# remote.net
KiCad netlist of a schematic drawn in EAGLE
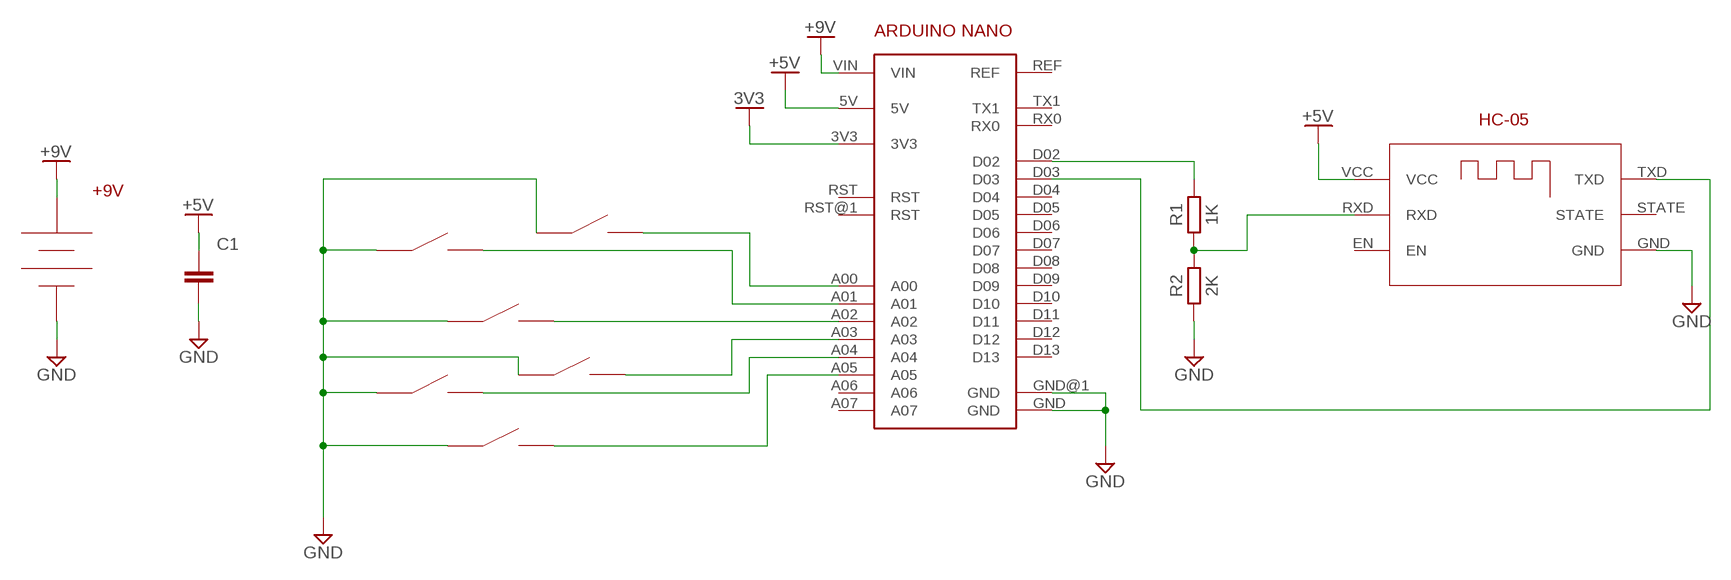
[diagram p0: schematic, sheet 1]

(export (version "E")
  (design (tool "Eeschema 10.0.6"))
  (components
    (comp (ref "C1")
      (value "C_RADIAL-12.5MM-DIA")
      (footprint "eagle-import:CAPRD550W60D1025H1250B")
      (libsource (lib "eagle-import") (part "CRADIAL-12.5MM-DIA_"))
    )
    (comp (ref "DOWN")
      (value "TACT_SWITCH_6MM")
      (footprint "eagle-import:TACT_SWITCH_6MM")
      (libsource (lib "eagle-import") (part "TACT_SWITCH_6MM"))
    )
    (comp (ref "LEFT")
      (value "TACT_SWITCH_6MM")
      (footprint "eagle-import:TACT_SWITCH_6MM")
      (libsource (lib "eagle-import") (part "TACT_SWITCH_6MM"))
    )
    (comp (ref "LEFT_BUMPER")
      (value "TACT_SWITCH_6MM")
      (footprint "eagle-import:TACT_SWITCH_6MM")
      (libsource (lib "eagle-import") (part "TACT_SWITCH_6MM"))
    )
    (comp (ref "R1")
      (value "1K")
      (footprint "eagle-import:RESAD1176W63L850D250B")
      (libsource (lib "eagle-import") (part "RAXIAL-11.7MM-PITCH_"))
    )
    (comp (ref "R2")
      (value "2K")
      (footprint "eagle-import:RESAD1176W63L850D250B")
      (libsource (lib "eagle-import") (part "RAXIAL-11.7MM-PITCH_"))
    )
    (comp (ref "RIGHT")
      (value "TACT_SWITCH_6MM")
      (footprint "eagle-import:TACT_SWITCH_6MM")
      (libsource (lib "eagle-import") (part "TACT_SWITCH_6MM"))
    )
    (comp (ref "RIGHT_BUMPER")
      (value "TACT_SWITCH_6MM")
      (footprint "eagle-import:TACT_SWITCH_6MM")
      (libsource (lib "eagle-import") (part "TACT_SWITCH_6MM"))
    )
    (comp (ref "U$1")
      (value "9V_BATTERY")
      (footprint "eagle-import:9V_BATTERY")
      (libsource (lib "eagle-import") (part "9V_BATTERY"))
    )
    (comp (ref "U$2")
      (value "HC-05")
      (footprint "eagle-import:HC-05")
      (libsource (lib "eagle-import") (part "HC-05"))
    )
    (comp (ref "U$9")
      (value "ARDUINO-NANO-V3")
      (footprint "eagle-import:ARDUINO-NANO-V3")
      (libsource (lib "eagle-import") (part "ARDUINO-NANO-V3"))
    )
    (comp (ref "UP")
      (value "TACT_SWITCH_6MM")
      (footprint "eagle-import:TACT_SWITCH_6MM")
      (libsource (lib "eagle-import") (part "TACT_SWITCH_6MM"))
    )
  )
  (nets
    (net (code "1") (name "+5V") (class "Default")
      (node (ref "C1") (pin "1") (pinfunction "1_1") (pintype "passive"))
      (node (ref "U$2") (pin "VCC") (pinfunction "VCC_VCC") (pintype "bidirectional"))
      (node (ref "U$9") (pin "5V") (pinfunction "5V_5V") (pintype "bidirectional"))
    )
    (net (code "2") (name "+9V") (class "Default")
      (node (ref "U$1") (pin "POS") (pinfunction "9V_POS") (pintype "bidirectional"))
      (node (ref "U$9") (pin "VIN") (pinfunction "VIN_VIN") (pintype "bidirectional"))
    )
    (net (code "3") (name "3V3") (class "Default")
      (node (ref "U$9") (pin "3V3") (pinfunction "3V3_3V3") (pintype "bidirectional"))
    )
    (net (code "4") (name "GND") (class "Default")
      (node (ref "C1") (pin "2") (pinfunction "2_2") (pintype "passive"))
      (node (ref "DOWN") (pin "A1") (pinfunction "A_A1") (pintype "bidirectional"))
      (node (ref "DOWN") (pin "A2") (pinfunction "A_A2") (pintype "bidirectional"))
      (node (ref "LEFT") (pin "A1") (pinfunction "A_A1") (pintype "bidirectional"))
      (node (ref "LEFT") (pin "A2") (pinfunction "A_A2") (pintype "bidirectional"))
      (node (ref "LEFT_BUMPER") (pin "A1") (pinfunction "A_A1") (pintype "bidirectional"))
      (node (ref "LEFT_BUMPER") (pin "A2") (pinfunction "A_A2") (pintype "bidirectional"))
      (node (ref "R2") (pin "1") (pinfunction "1_1") (pintype "passive"))
      (node (ref "RIGHT") (pin "A1") (pinfunction "A_A1") (pintype "bidirectional"))
      (node (ref "RIGHT") (pin "A2") (pinfunction "A_A2") (pintype "bidirectional"))
      (node (ref "RIGHT_BUMPER") (pin "A1") (pinfunction "A_A1") (pintype "bidirectional"))
      (node (ref "RIGHT_BUMPER") (pin "A2") (pinfunction "A_A2") (pintype "bidirectional"))
      (node (ref "U$1") (pin "NEG") (pinfunction "NEG_NEG") (pintype "bidirectional"))
      (node (ref "U$2") (pin "GND") (pinfunction "GND_GND") (pintype "bidirectional"))
      (node (ref "U$9") (pin "GND") (pinfunction "GND_GND") (pintype "bidirectional"))
      (node (ref "U$9") (pin "GND@1") (pinfunction "GND_GND@1") (pintype "bidirectional"))
      (node (ref "UP") (pin "A1") (pinfunction "A_A1") (pintype "bidirectional"))
      (node (ref "UP") (pin "A2") (pinfunction "A_A2") (pintype "bidirectional"))
    )
    (net (code "5") (name "Net-(DOWN-B-PadB1)") (class "Default")
      (node (ref "DOWN") (pin "B1") (pinfunction "B_B1") (pintype "bidirectional"))
      (node (ref "DOWN") (pin "B2") (pinfunction "B_B2") (pintype "bidirectional"))
      (node (ref "U$9") (pin "A05") (pinfunction "A05_A05") (pintype "bidirectional"))
    )
    (net (code "6") (name "Net-(LEFT-B-PadB1)") (class "Default")
      (node (ref "LEFT") (pin "B1") (pinfunction "B_B1") (pintype "bidirectional"))
      (node (ref "LEFT") (pin "B2") (pinfunction "B_B2") (pintype "bidirectional"))
      (node (ref "U$9") (pin "A04") (pinfunction "A04_A04") (pintype "bidirectional"))
    )
    (net (code "7") (name "Net-(LEFT_BUMPER-B-PadB1)") (class "Default")
      (node (ref "LEFT_BUMPER") (pin "B1") (pinfunction "B_B1") (pintype "bidirectional"))
      (node (ref "LEFT_BUMPER") (pin "B2") (pinfunction "B_B2") (pintype "bidirectional"))
      (node (ref "U$9") (pin "A01") (pinfunction "A01_A01") (pintype "bidirectional"))
    )
    (net (code "8") (name "Net-(R1-Pad1)") (class "Default")
      (node (ref "R1") (pin "1") (pinfunction "1_1") (pintype "passive"))
      (node (ref "R2") (pin "2") (pinfunction "2_2") (pintype "passive"))
      (node (ref "U$2") (pin "RXD") (pinfunction "RXD_RXD") (pintype "bidirectional"))
    )
    (net (code "9") (name "Net-(R1-Pad2)") (class "Default")
      (node (ref "R1") (pin "2") (pinfunction "2_2") (pintype "passive"))
      (node (ref "U$9") (pin "D02") (pinfunction "D02_D02") (pintype "bidirectional"))
    )
    (net (code "10") (name "Net-(RIGHT-B-PadB1)") (class "Default")
      (node (ref "RIGHT") (pin "B1") (pinfunction "B_B1") (pintype "bidirectional"))
      (node (ref "RIGHT") (pin "B2") (pinfunction "B_B2") (pintype "bidirectional"))
      (node (ref "U$9") (pin "A03") (pinfunction "A03_A03") (pintype "bidirectional"))
    )
    (net (code "11") (name "Net-(RIGHT_BUMPER-B-PadB1)") (class "Default")
      (node (ref "RIGHT_BUMPER") (pin "B1") (pinfunction "B_B1") (pintype "bidirectional"))
      (node (ref "RIGHT_BUMPER") (pin "B2") (pinfunction "B_B2") (pintype "bidirectional"))
      (node (ref "U$9") (pin "A00") (pinfunction "A00_A00") (pintype "bidirectional"))
    )
    (net (code "12") (name "Net-(U$2-PadTXD)") (class "Default")
      (node (ref "U$2") (pin "TXD") (pinfunction "TXD_TXD") (pintype "bidirectional"))
      (node (ref "U$9") (pin "D03") (pinfunction "D03_D03") (pintype "bidirectional"))
    )
    (net (code "13") (name "Net-(U$9-PadA02)") (class "Default")
      (node (ref "U$9") (pin "A02") (pinfunction "A02_A02") (pintype "bidirectional"))
      (node (ref "UP") (pin "B1") (pinfunction "B_B1") (pintype "bidirectional"))
      (node (ref "UP") (pin "B2") (pinfunction "B_B2") (pintype "bidirectional"))
    )
    (net (code "14") (name "unconnected-(U$2-PadEN)") (class "Default")
      (node (ref "U$2") (pin "EN") (pinfunction "EN_EN") (pintype "bidirectional"))
    )
    (net (code "15") (name "unconnected-(U$2-PadSTATE)") (class "Default")
      (node (ref "U$2") (pin "STATE") (pinfunction "STATE_STATE") (pintype "bidirectional"))
    )
    (net (code "16") (name "unconnected-(U$9-PadA06)") (class "Default")
      (node (ref "U$9") (pin "A06") (pinfunction "A06_A06") (pintype "bidirectional"))
    )
    (net (code "17") (name "unconnected-(U$9-PadA07)") (class "Default")
      (node (ref "U$9") (pin "A07") (pinfunction "A07_A07") (pintype "bidirectional"))
    )
    (net (code "18") (name "unconnected-(U$9-PadD04)") (class "Default")
      (node (ref "U$9") (pin "D04") (pinfunction "D04_D04") (pintype "bidirectional"))
    )
    (net (code "19") (name "unconnected-(U$9-PadD05)") (class "Default")
      (node (ref "U$9") (pin "D05") (pinfunction "D05_D05") (pintype "bidirectional"))
    )
    (net (code "20") (name "unconnected-(U$9-PadD06)") (class "Default")
      (node (ref "U$9") (pin "D06") (pinfunction "D06_D06") (pintype "bidirectional"))
    )
    (net (code "21") (name "unconnected-(U$9-PadD07)") (class "Default")
      (node (ref "U$9") (pin "D07") (pinfunction "D07_D07") (pintype "bidirectional"))
    )
    (net (code "22") (name "unconnected-(U$9-PadD08)") (class "Default")
      (node (ref "U$9") (pin "D08") (pinfunction "D08_D08") (pintype "bidirectional"))
    )
    (net (code "23") (name "unconnected-(U$9-PadD09)") (class "Default")
      (node (ref "U$9") (pin "D09") (pinfunction "D09_D09") (pintype "bidirectional"))
    )
    (net (code "24") (name "unconnected-(U$9-PadD10)") (class "Default")
      (node (ref "U$9") (pin "D10") (pinfunction "D10_D10") (pintype "bidirectional"))
    )
    (net (code "25") (name "unconnected-(U$9-PadD11)") (class "Default")
      (node (ref "U$9") (pin "D11") (pinfunction "D11_D11") (pintype "bidirectional"))
    )
    (net (code "26") (name "unconnected-(U$9-PadD12)") (class "Default")
      (node (ref "U$9") (pin "D12") (pinfunction "D12_D12") (pintype "bidirectional"))
    )
    (net (code "27") (name "unconnected-(U$9-PadD13)") (class "Default")
      (node (ref "U$9") (pin "D13") (pinfunction "D13_D13") (pintype "bidirectional"))
    )
    (net (code "28") (name "unconnected-(U$9-PadREF)") (class "Default")
      (node (ref "U$9") (pin "REF") (pinfunction "REF_REF") (pintype "bidirectional"))
    )
    (net (code "29") (name "unconnected-(U$9-PadRST)") (class "Default")
      (node (ref "U$9") (pin "RST") (pinfunction "RST_RST") (pintype "bidirectional"))
    )
    (net (code "30") (name "unconnected-(U$9-PadRX0)") (class "Default")
      (node (ref "U$9") (pin "RX0") (pinfunction "RX0_RX0") (pintype "bidirectional"))
    )
    (net (code "31") (name "unconnected-(U$9-PadTX1)") (class "Default")
      (node (ref "U$9") (pin "TX1") (pinfunction "TX1_TX1") (pintype "bidirectional"))
    )
    (net (code "32") (name "unconnected-(U$9-RST-PadRST@1)") (class "Default")
      (node (ref "U$9") (pin "RST@1") (pinfunction "RST_RST@1") (pintype "bidirectional"))
    )
  )
)
